# ESP32USBC.net
KiCad netlist of a schematic drawn in Altium Designer
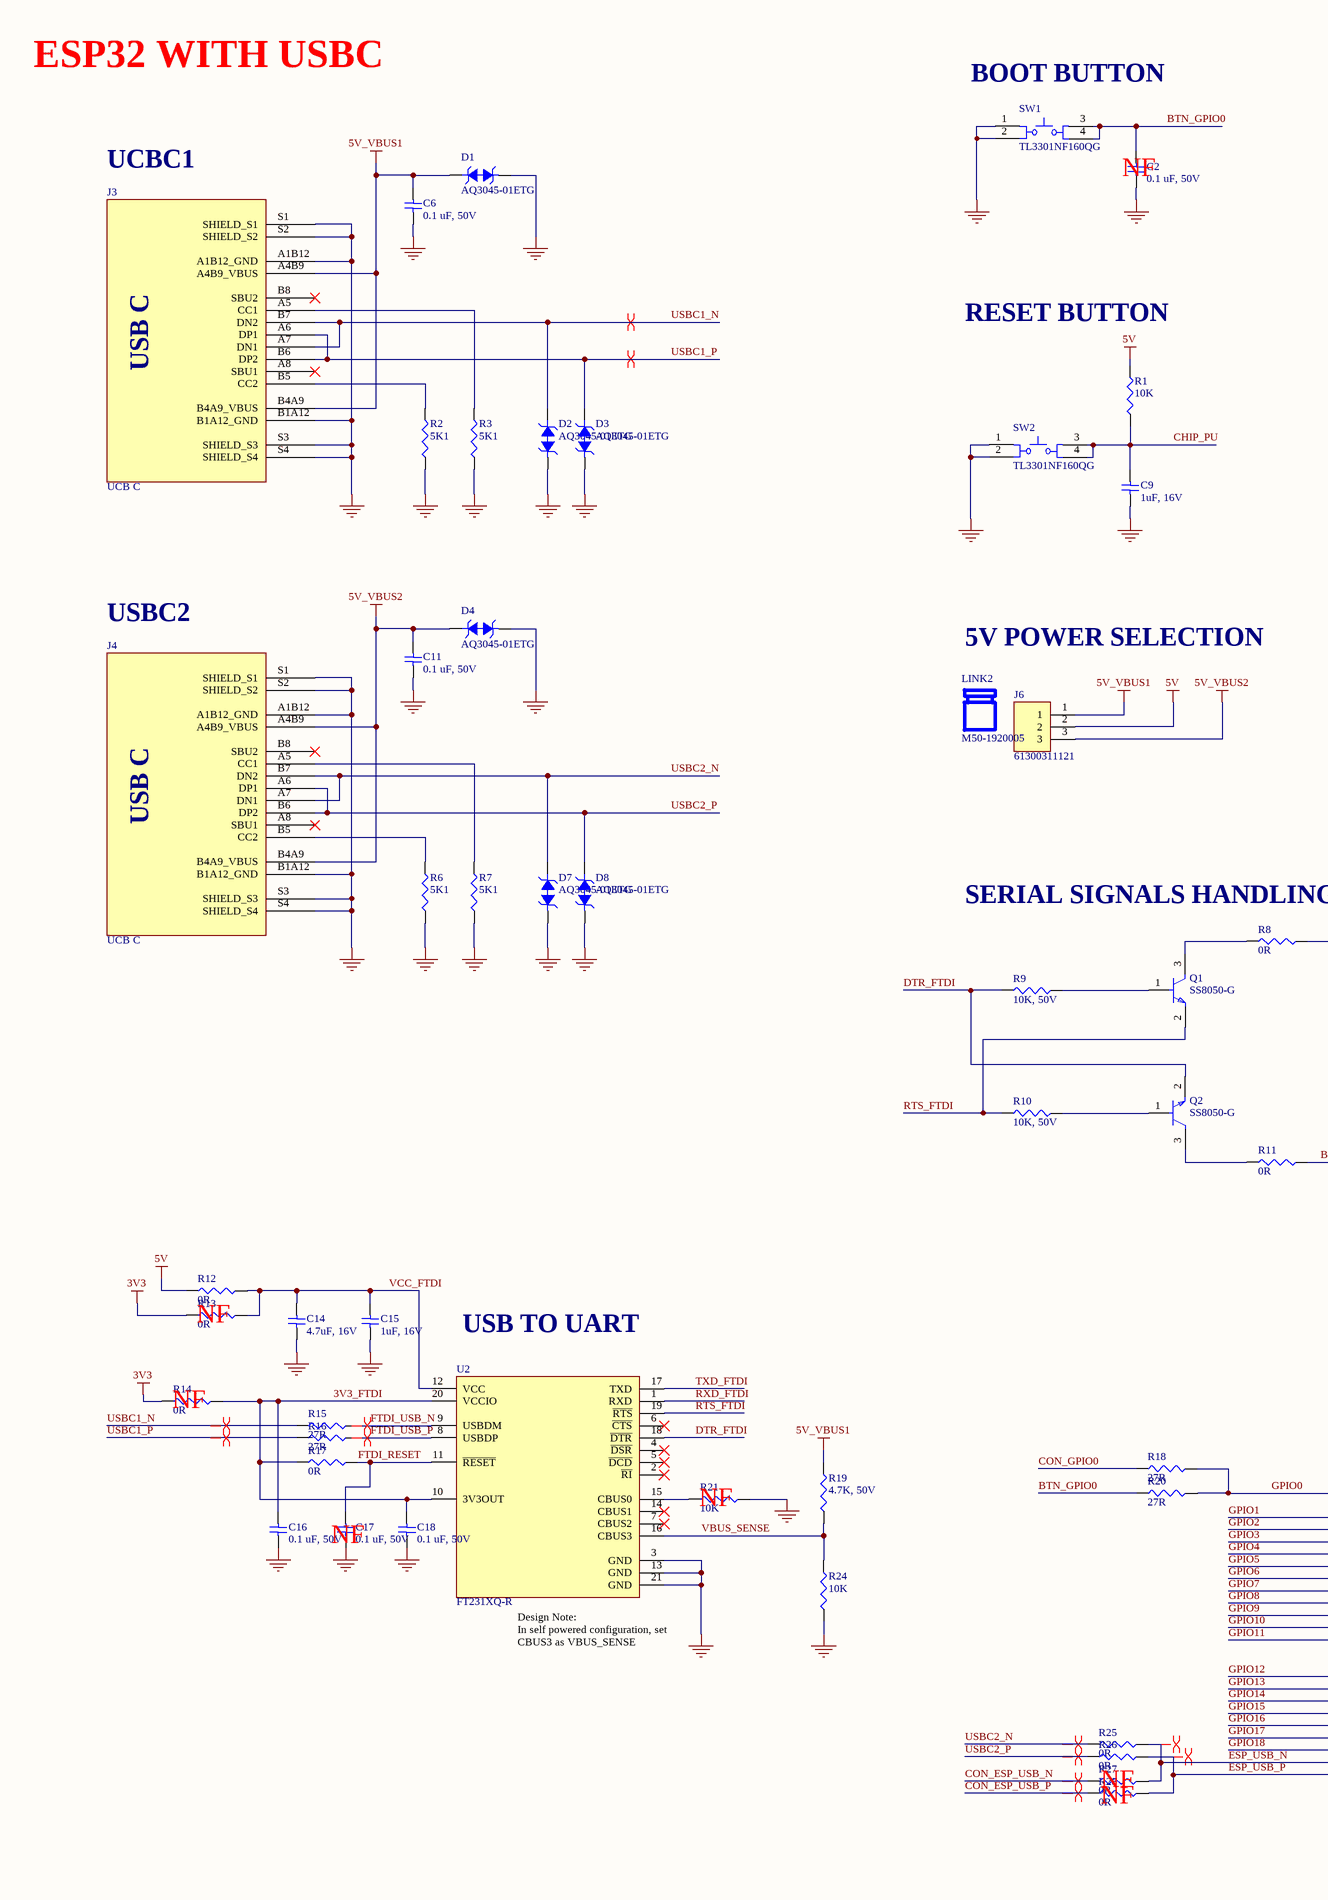
[diagram p0: ESP32USBC.SchDoc, left]
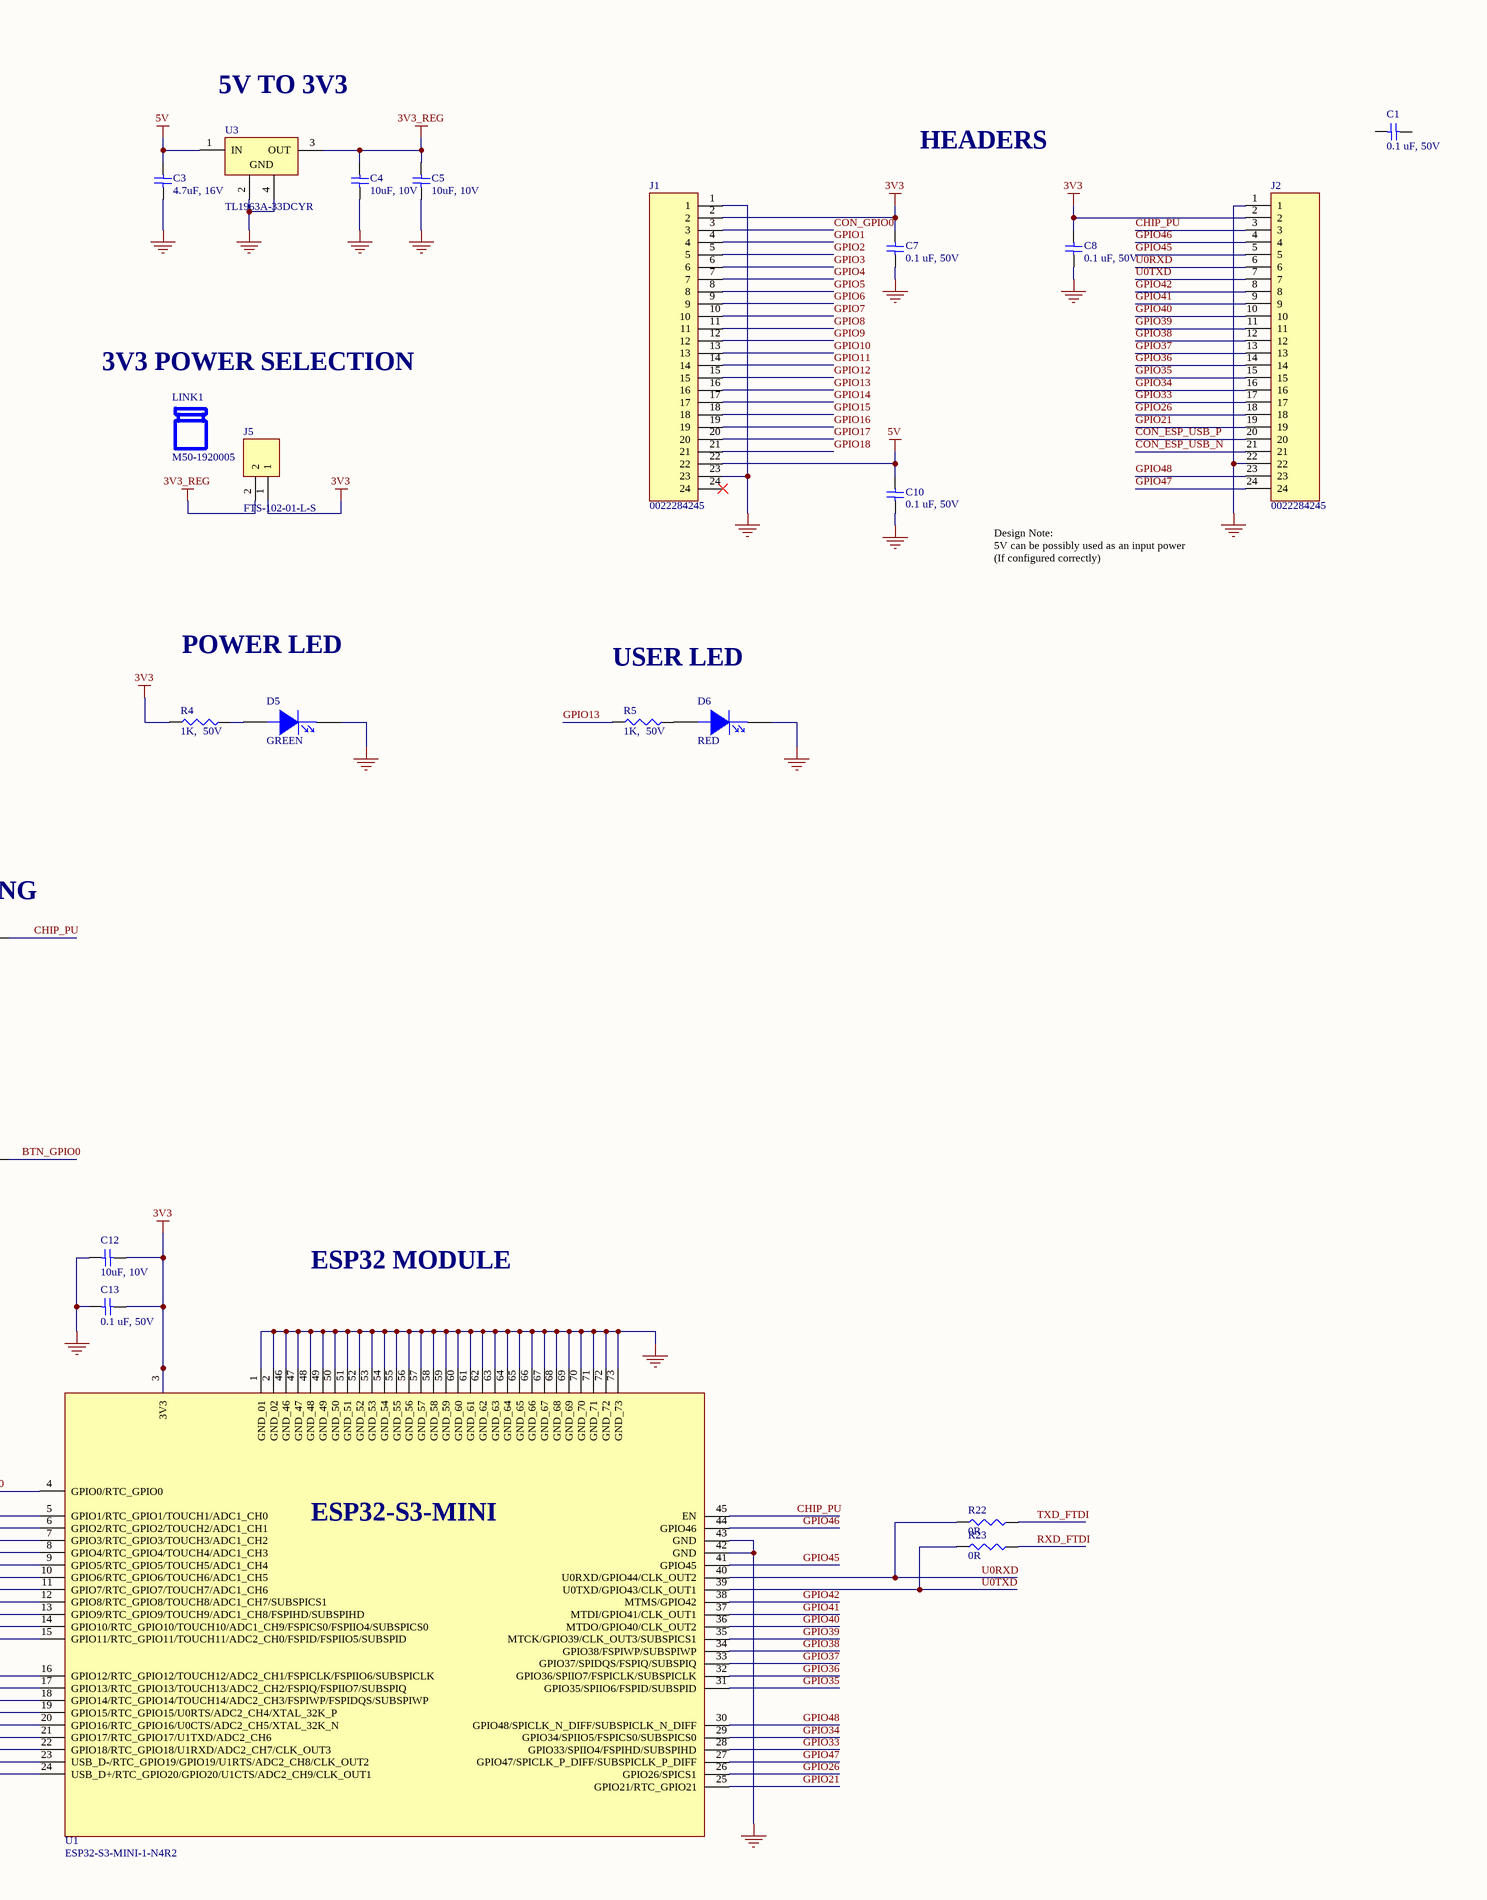
[diagram p1: ESP32USBC.SchDoc, right]

(export (version "E")
  (design (tool "Eeschema 10.0.6"))
  (components
    (comp (ref "C1")
      (value "0.1 uF, 50V")
      (footprint "CAPC1005X55N")
      (fields
        (field (name "MANUFACTURER") "Samsung")
        (field (name "MANUFACTURER PART NUMBER") "CL05B104KB54PNC")
        (field (name "LCSC PART NUMBER") "C307331")
      )
      (libsource (lib "Schlib") (part "CL05B104KB54PNC"))
    )
    (comp (ref "C2")
      (value "0.1 uF, 50V")
      (footprint "CAPC1005X55N")
      (fields
        (field (name "MANUFACTURER") "Samsung")
        (field (name "MANUFACTURER PART NUMBER") "CL05B104KB54PNC")
        (field (name "LCSC PART NUMBER") "C307331")
      )
      (libsource (lib "Schlib") (part "CL05B104KB54PNC"))
    )
    (comp (ref "C3")
      (value "4.7uF, 16V")
      (footprint "CAPC1005X55N")
      (description "CAP CER 4.7UF 16V X5R 0402")
      (fields
        (field (name "MANUFACTURER") "Samsung")
        (field (name "MANUFACTURER PART NUMBER") "CL05A475MO5NUNC")
      )
      (libsource (lib "Schlib") (part "CL05A475MO5NUNC"))
    )
    (comp (ref "C4")
      (value "10uF, 10V")
      (footprint "CAPC1005X55N")
      (description "10V 10uF X5R ±20% 0402 Multilayer Ceramic Capacitors MLCC - SMD/SMT ROHS")
      (fields
        (field (name "MANUFACTURER") "Samsung")
        (field (name "MANUFACTURER PART NUMBER") "CL05A106MP8NUB8")
      )
      (libsource (lib "Schlib") (part "CL05A106MP8NUB8"))
    )
    (comp (ref "C5")
      (value "10uF, 10V")
      (footprint "CAPC1005X55N")
      (description "10V 10uF X5R ±20% 0402 Multilayer Ceramic Capacitors MLCC - SMD/SMT ROHS")
      (fields
        (field (name "MANUFACTURER") "Samsung")
        (field (name "MANUFACTURER PART NUMBER") "CL05A106MP8NUB8")
      )
      (libsource (lib "Schlib") (part "CL05A106MP8NUB8"))
    )
    (comp (ref "C6")
      (value "0.1 uF, 50V")
      (footprint "CAPC1005X55N")
      (fields
        (field (name "MANUFACTURER") "Samsung")
        (field (name "MANUFACTURER PART NUMBER") "CL05B104KB54PNC")
        (field (name "LCSC PART NUMBER") "C307331")
      )
      (libsource (lib "Schlib") (part "CL05B104KB54PNC"))
    )
    (comp (ref "C7")
      (value "0.1 uF, 50V")
      (footprint "CAPC1005X55N")
      (fields
        (field (name "MANUFACTURER") "Samsung")
        (field (name "MANUFACTURER PART NUMBER") "CL05B104KB54PNC")
        (field (name "LCSC PART NUMBER") "C307331")
      )
      (libsource (lib "Schlib") (part "CL05B104KB54PNC"))
    )
    (comp (ref "C8")
      (value "0.1 uF, 50V")
      (footprint "CAPC1005X55N")
      (fields
        (field (name "MANUFACTURER") "Samsung")
        (field (name "MANUFACTURER PART NUMBER") "CL05B104KB54PNC")
        (field (name "LCSC PART NUMBER") "C307331")
      )
      (libsource (lib "Schlib") (part "CL05B104KB54PNC"))
    )
    (comp (ref "C9")
      (value "1uF, 16V")
      (footprint "CAPC1005X55N")
      (description "1 µF ±10% 16V Ceramic Capacitor X5R 0402 (1005 Metric)")
      (fields
        (field (name "MANUFACTURER") "Samsung")
        (field (name "MANUFACTURER PART NUMBER") "CL05A105KO5NNNC")
      )
      (libsource (lib "Schlib") (part "CL05A105KO5NNNC"))
    )
    (comp (ref "C10")
      (value "0.1 uF, 50V")
      (footprint "CAPC1005X55N")
      (fields
        (field (name "MANUFACTURER") "Samsung")
        (field (name "MANUFACTURER PART NUMBER") "CL05B104KB54PNC")
        (field (name "LCSC PART NUMBER") "C307331")
      )
      (libsource (lib "Schlib") (part "CL05B104KB54PNC"))
    )
    (comp (ref "C11")
      (value "0.1 uF, 50V")
      (footprint "CAPC1005X55N")
      (fields
        (field (name "MANUFACTURER") "Samsung")
        (field (name "MANUFACTURER PART NUMBER") "CL05B104KB54PNC")
        (field (name "LCSC PART NUMBER") "C307331")
      )
      (libsource (lib "Schlib") (part "CL05B104KB54PNC"))
    )
    (comp (ref "C12")
      (value "10uF, 10V")
      (footprint "CAPC1005X55N")
      (description "10V 10uF X5R ±20% 0402 Multilayer Ceramic Capacitors MLCC - SMD/SMT ROHS")
      (fields
        (field (name "MANUFACTURER") "Samsung")
        (field (name "MANUFACTURER PART NUMBER") "CL05A106MP8NUB8")
      )
      (libsource (lib "Schlib") (part "CL05A106MP8NUB8"))
    )
    (comp (ref "C13")
      (value "0.1 uF, 50V")
      (footprint "CAPC1005X55N")
      (fields
        (field (name "MANUFACTURER") "Samsung")
        (field (name "MANUFACTURER PART NUMBER") "CL05B104KB54PNC")
        (field (name "LCSC PART NUMBER") "C307331")
      )
      (libsource (lib "Schlib") (part "CL05B104KB54PNC"))
    )
    (comp (ref "C14")
      (value "4.7uF, 16V")
      (footprint "CAPC1005X55N")
      (description "CAP CER 4.7UF 16V X5R 0402")
      (fields
        (field (name "MANUFACTURER") "Samsung")
        (field (name "MANUFACTURER PART NUMBER") "CL05A475MO5NUNC")
      )
      (libsource (lib "Schlib") (part "CL05A475MO5NUNC"))
    )
    (comp (ref "C15")
      (value "1uF, 16V")
      (footprint "CAPC1005X55N")
      (description "1 µF ±10% 16V Ceramic Capacitor X5R 0402 (1005 Metric)")
      (fields
        (field (name "MANUFACTURER") "Samsung")
        (field (name "MANUFACTURER PART NUMBER") "CL05A105KO5NNNC")
      )
      (libsource (lib "Schlib") (part "CL05A105KO5NNNC"))
    )
    (comp (ref "C16")
      (value "0.1 uF, 50V")
      (footprint "CAPC1005X55N")
      (fields
        (field (name "MANUFACTURER") "Samsung")
        (field (name "MANUFACTURER PART NUMBER") "CL05B104KB54PNC")
        (field (name "LCSC PART NUMBER") "C307331")
      )
      (libsource (lib "Schlib") (part "CL05B104KB54PNC"))
    )
    (comp (ref "C17")
      (value "0.1 uF, 50V")
      (footprint "CAPC1005X55N")
      (fields
        (field (name "MANUFACTURER") "Samsung")
        (field (name "MANUFACTURER PART NUMBER") "CL05B104KB54PNC")
        (field (name "LCSC PART NUMBER") "C307331")
      )
      (libsource (lib "Schlib") (part "CL05B104KB54PNC"))
    )
    (comp (ref "C18")
      (value "0.1 uF, 50V")
      (footprint "CAPC1005X55N")
      (fields
        (field (name "MANUFACTURER") "Samsung")
        (field (name "MANUFACTURER PART NUMBER") "CL05B104KB54PNC")
        (field (name "LCSC PART NUMBER") "C307331")
      )
      (libsource (lib "Schlib") (part "CL05B104KB54PNC"))
    )
    (comp (ref "D1")
      (value "AQ3045-01ETG")
      (footprint "SOD882")
      (description "12V Clamp 3A (8/20µs) Ipp Tvs Diode Surface Mount SOD-882")
      (fields (field (name "MANUFACTURER") "Littelfuse") (field (name "LCSC PART NUMBER") "C3710326"))
      (libsource (lib "Schlib") (part "AQ3045-01ETG"))
    )
    (comp (ref "D2")
      (value "AQ3045-01ETG")
      (footprint "SOD882")
      (description "12V Clamp 3A (8/20µs) Ipp Tvs Diode Surface Mount SOD-882")
      (fields (field (name "MANUFACTURER") "Littelfuse") (field (name "LCSC PART NUMBER") "C3710326"))
      (libsource (lib "Schlib") (part "AQ3045-01ETG"))
    )
    (comp (ref "D3")
      (value "AQ3045-01ETG")
      (footprint "SOD882")
      (description "12V Clamp 3A (8/20µs) Ipp Tvs Diode Surface Mount SOD-882")
      (fields (field (name "MANUFACTURER") "Littelfuse") (field (name "LCSC PART NUMBER") "C3710326"))
      (libsource (lib "Schlib") (part "AQ3045-01ETG"))
    )
    (comp (ref "D4")
      (value "AQ3045-01ETG")
      (footprint "SOD882")
      (description "12V Clamp 3A (8/20µs) Ipp Tvs Diode Surface Mount SOD-882")
      (fields (field (name "MANUFACTURER") "Littelfuse") (field (name "LCSC PART NUMBER") "C3710326"))
      (libsource (lib "Schlib") (part "AQ3045-01ETG"))
    )
    (comp (ref "D5")
      (value "GREEN")
      (footprint "LED0402G")
      (description "LED YLW-GRN 0402 SMD")
      (fields
        (field (name "MANUFACTURER") "Vishay")
        (field (name "MANUFACTURER PART NUMBER") "VLMG1500-GS08")
      )
      (libsource (lib "Schlib") (part "VLMG1500-GS08"))
    )
    (comp (ref "D6")
      (value "RED")
      (footprint "LED0402R")
      (description "LED RED 0402 SMD")
      (fields
        (field (name "MANUFACTURER") "Vishay")
        (field (name "MANUFACTURER PART NUMBER") "VLMS1500-GS08")
      )
      (libsource (lib "Schlib") (part "VLMS1500-GS08"))
    )
    (comp (ref "D7")
      (value "AQ3045-01ETG")
      (footprint "SOD882")
      (description "12V Clamp 3A (8/20µs) Ipp Tvs Diode Surface Mount SOD-882")
      (fields (field (name "MANUFACTURER") "Littelfuse") (field (name "LCSC PART NUMBER") "C3710326"))
      (libsource (lib "Schlib") (part "AQ3045-01ETG"))
    )
    (comp (ref "D8")
      (value "AQ3045-01ETG")
      (footprint "SOD882")
      (description "12V Clamp 3A (8/20µs) Ipp Tvs Diode Surface Mount SOD-882")
      (fields (field (name "MANUFACTURER") "Littelfuse") (field (name "LCSC PART NUMBER") "C3710326"))
      (libsource (lib "Schlib") (part "AQ3045-01ETG"))
    )
    (comp (ref "J1")
      (value "0022284245")
      (footprint "HDR_1x24_2.54MM")
      (description "CONN HEADER VERT 24POS 2.54MM")
      (fields (field (name "MANUFACTURER") "Molex") (field (name "LCSC PART NUMBER") "C7145888"))
      (libsource (lib "Schlib") (part "0022284245"))
    )
    (comp (ref "J2")
      (value "0022284245")
      (footprint "HDR_1x24_2.54MM")
      (description "CONN HEADER VERT 24POS 2.54MM")
      (fields (field (name "MANUFACTURER") "Molex") (field (name "LCSC PART NUMBER") "C7145888"))
      (libsource (lib "") (part "0022284245_1"))
    )
    (comp (ref "J3")
      (value "UCB C")
      (footprint "FP-2171790001-MFG")
      (fields
        (field (name "MANUFACTURER") "Molex")
        (field (name "MANUFACTURER PART NUMBER") "217179-0001")
        (field (name "LCSC PART NUMBER") "C3197684")
      )
      (libsource (lib "Schlib") (part "217179-0001"))
    )
    (comp (ref "J4")
      (value "UCB C")
      (footprint "FP-2171790001-MFG")
      (fields
        (field (name "MANUFACTURER") "Molex")
        (field (name "MANUFACTURER PART NUMBER") "217179-0001")
        (field (name "LCSC PART NUMBER") "C3197684")
      )
      (libsource (lib "Schlib") (part "217179-0001"))
    )
    (comp (ref "J5")
      (value "FTS-102-01-L-S")
      (footprint "HDR_1x2_1.27MM")
      (description "Board Connector, 2 Contact(s), 1 Row(s), Male, Straight, Solder Terminal")
      (fields (field (name "MANUFACTURER") "Samtec") (field (name "LCSC PART NUMBER") "C7194937"))
      (libsource (lib "Schlib") (part "FTS-102-01-L-S"))
    )
    (comp (ref "J6")
      (value "61300311121")
      (footprint "HDR_1x3_2.54MM")
      (description "CONN HEADER VERT 3POS 2.54MM")
      (fields (field (name "MANUFACTURER") "Wurth Electronics"))
      (libsource (lib "Schlib") (part "61300311121"))
    )
    (comp (ref "LINK1")
      (value "M50-1920005")
      (description "CONN SHUNT 1.27MM RED")
      (fields (field (name "MANUFACTURER") "Harwin") (field (name "LCSC PART NUMBER") "C6985646"))
      (libsource (lib "Schlib") (part "M50-1920005"))
    )
    (comp (ref "LINK2")
      (value "M50-1920005")
      (description "CONN SHUNT 1.27MM RED")
      (fields (field (name "MANUFACTURER") "Harwin") (field (name "LCSC PART NUMBER") "C6985646"))
      (libsource (lib "Schlib") (part "M50-1920005"))
    )
    (comp (ref "Q1")
      (value "SS8050-G")
      (footprint "FP-SS8050-G-IPC_B")
      (description "TRANS NPN 25V 1.5A SOT23-3")
      (fields (field (name "MANUFACTURER") "Comchip") (field (name "LCSC PART NUMBER") "C164886"))
      (libsource (lib "Schlib") (part "SS8050-G"))
    )
    (comp (ref "Q2")
      (value "SS8050-G")
      (footprint "FP-SS8050-G-IPC_B")
      (description "TRANS NPN 25V 1.5A SOT23-3")
      (fields (field (name "MANUFACTURER") "Comchip") (field (name "LCSC PART NUMBER") "C164886"))
      (libsource (lib "Schlib") (part "SS8050-G"))
    )
    (comp (ref "R1")
      (value "10K")
      (footprint "RESC1005X40N")
      (fields
        (field (name "MANUFACTURER") "Samsung")
        (field (name "MANUFACTURER PART NUMBER") "RC1005F103CS")
        (field (name "TOLERANCE") "1%")
      )
      (libsource (lib "Schlib") (part "RC1005F103CS"))
    )
    (comp (ref "R2")
      (value "5K1")
      (footprint "RESC1005X40N")
      (description "5.1 kOhms ±1% 0.063W, 1/16W Chip Resistor 0402 (1005 Metric) Moisture Resistant Thick Film")
      (fields
        (field (name "MANUFACTURER") "Yageo")
        (field (name "MANUFACTURER PART NUMBER") "RC0402FR-075K1L")
      )
      (libsource (lib "Schlib") (part "RC0402FR-075K1L"))
    )
    (comp (ref "R3")
      (value "5K1")
      (footprint "RESC1005X40N")
      (description "5.1 kOhms ±1% 0.063W, 1/16W Chip Resistor 0402 (1005 Metric) Moisture Resistant Thick Film")
      (fields
        (field (name "MANUFACTURER") "Yageo")
        (field (name "MANUFACTURER PART NUMBER") "RC0402FR-075K1L")
      )
      (libsource (lib "Schlib") (part "RC0402FR-075K1L"))
    )
    (comp (ref "R4")
      (value "1K,  50V")
      (footprint "RESC1005X40N")
      (description "RES 1K OHM 5% 1/16W 0402")
      (fields
        (field (name "MANUFACTURER") "Yageo")
        (field (name "MANUFACTURER PART NUMBER") "RC0402JR-071KL")
      )
      (libsource (lib "Schlib") (part "RC0402JR-071KL"))
    )
    (comp (ref "R5")
      (value "1K,  50V")
      (footprint "RESC1005X40N")
      (description "RES 1K OHM 5% 1/16W 0402")
      (fields
        (field (name "MANUFACTURER") "Yageo")
        (field (name "MANUFACTURER PART NUMBER") "RC0402JR-071KL")
      )
      (libsource (lib "Schlib") (part "RC0402JR-071KL"))
    )
    (comp (ref "R6")
      (value "5K1")
      (footprint "RESC1005X40N")
      (description "5.1 kOhms ±1% 0.063W, 1/16W Chip Resistor 0402 (1005 Metric) Moisture Resistant Thick Film")
      (fields
        (field (name "MANUFACTURER") "Yageo")
        (field (name "MANUFACTURER PART NUMBER") "RC0402FR-075K1L")
      )
      (libsource (lib "Schlib") (part "RC0402FR-075K1L"))
    )
    (comp (ref "R7")
      (value "5K1")
      (footprint "RESC1005X40N")
      (description "5.1 kOhms ±1% 0.063W, 1/16W Chip Resistor 0402 (1005 Metric) Moisture Resistant Thick Film")
      (fields
        (field (name "MANUFACTURER") "Yageo")
        (field (name "MANUFACTURER PART NUMBER") "RC0402FR-075K1L")
      )
      (libsource (lib "Schlib") (part "RC0402FR-075K1L"))
    )
    (comp (ref "R8")
      (value "0R")
      (footprint "RESC1005X40N")
      (description "RES 0 OHM JUMPER 1/16W 0402")
      (fields
        (field (name "MANUFACTURER") "Yageo")
        (field (name "MANUFACTURER PART NUMBER") "RC0402JR-070RL")
      )
      (libsource (lib "Schlib") (part "RC0402JR-070RL"))
    )
    (comp (ref "R9")
      (value "10K, 50V")
      (footprint "RESC1005X40N")
      (description "RES 10K OHM 1% 1/16W 0402")
      (fields
        (field (name "MANUFACTURER") "Yageo")
        (field (name "MANUFACTURER PART NUMBER") "RC0402FR-0710KL")
      )
      (libsource (lib "Schlib") (part "RC0402FR-0710KL"))
    )
    (comp (ref "R10")
      (value "10K, 50V")
      (footprint "RESC1005X40N")
      (description "RES 10K OHM 1% 1/16W 0402")
      (fields
        (field (name "MANUFACTURER") "Yageo")
        (field (name "MANUFACTURER PART NUMBER") "RC0402FR-0710KL")
      )
      (libsource (lib "Schlib") (part "RC0402FR-0710KL"))
    )
    (comp (ref "R11")
      (value "0R")
      (footprint "RESC1005X40N")
      (description "RES 0 OHM JUMPER 1/16W 0402")
      (fields
        (field (name "MANUFACTURER") "Yageo")
        (field (name "MANUFACTURER PART NUMBER") "RC0402JR-070RL")
      )
      (libsource (lib "Schlib") (part "RC0402JR-070RL"))
    )
    (comp (ref "R12")
      (value "0R")
      (footprint "RESC1005X40N")
      (description "RES 0 OHM JUMPER 1/16W 0402")
      (fields
        (field (name "MANUFACTURER") "Yageo")
        (field (name "MANUFACTURER PART NUMBER") "RC0402JR-070RL")
      )
      (libsource (lib "Schlib") (part "RC0402JR-070RL"))
    )
    (comp (ref "R13")
      (value "0R")
      (footprint "RESC1005X40N")
      (description "RES 0 OHM JUMPER 1/16W 0402")
      (fields
        (field (name "MANUFACTURER") "Yageo")
        (field (name "MANUFACTURER PART NUMBER") "RC0402JR-070RL")
      )
      (libsource (lib "Schlib") (part "RC0402JR-070RL"))
    )
    (comp (ref "R14")
      (value "0R")
      (footprint "RESC1005X40N")
      (description "RES 0 OHM JUMPER 1/16W 0402")
      (fields
        (field (name "MANUFACTURER") "Yageo")
        (field (name "MANUFACTURER PART NUMBER") "RC0402JR-070RL")
      )
      (libsource (lib "Schlib") (part "RC0402JR-070RL"))
    )
    (comp (ref "R15")
      (value "27R")
      (footprint "RESC1005X40N")
      (description "27.4 Ohms ±1% 0.1W, 1/10W Chip Resistor 0402 (1005 Metric) Automotive AEC-Q200 Thick Film")
      (fields
        (field (name "MANUFACTURER") "Panasonic")
        (field (name "MANUFACTURER PART NUMBER") "ERJ-2RKF27R4X")
      )
      (libsource (lib "Schlib") (part "ERJ-2RKF27R4X"))
    )
    (comp (ref "R16")
      (value "27R")
      (footprint "RESC1005X40N")
      (description "27.4 Ohms ±1% 0.1W, 1/10W Chip Resistor 0402 (1005 Metric) Automotive AEC-Q200 Thick Film")
      (fields
        (field (name "MANUFACTURER") "Panasonic")
        (field (name "MANUFACTURER PART NUMBER") "ERJ-2RKF27R4X")
      )
      (libsource (lib "Schlib") (part "ERJ-2RKF27R4X"))
    )
    (comp (ref "R17")
      (value "0R")
      (footprint "RESC1005X40N")
      (description "RES 0 OHM JUMPER 1/16W 0402")
      (fields
        (field (name "MANUFACTURER") "Yageo")
        (field (name "MANUFACTURER PART NUMBER") "RC0402JR-070RL")
      )
      (libsource (lib "Schlib") (part "RC0402JR-070RL"))
    )
    (comp (ref "R18")
      (value "27R")
      (footprint "RESC1005X40N")
      (description "27.4 Ohms ±1% 0.1W, 1/10W Chip Resistor 0402 (1005 Metric) Automotive AEC-Q200 Thick Film")
      (fields
        (field (name "MANUFACTURER") "Panasonic")
        (field (name "MANUFACTURER PART NUMBER") "ERJ-2RKF27R4X")
      )
      (libsource (lib "Schlib") (part "ERJ-2RKF27R4X"))
    )
    (comp (ref "R19")
      (value "4.7K, 50V")
      (footprint "RESC1005X40N")
      (description "RES 4.7K OHM 5% 1/16W 0402")
      (fields
        (field (name "MANUFACTURER") "Yageo")
        (field (name "MANUFACTURER PART NUMBER") "RC0402JR-074K7L")
      )
      (libsource (lib "Schlib") (part "RC0402JR-074K7L"))
    )
    (comp (ref "R20")
      (value "27R")
      (footprint "RESC1005X40N")
      (description "27.4 Ohms ±1% 0.1W, 1/10W Chip Resistor 0402 (1005 Metric) Automotive AEC-Q200 Thick Film")
      (fields
        (field (name "MANUFACTURER") "Panasonic")
        (field (name "MANUFACTURER PART NUMBER") "ERJ-2RKF27R4X")
      )
      (libsource (lib "Schlib") (part "ERJ-2RKF27R4X"))
    )
    (comp (ref "R21")
      (value "10K")
      (footprint "RESC1005X40N")
      (fields
        (field (name "MANUFACTURER") "Samsung")
        (field (name "MANUFACTURER PART NUMBER") "RC1005F103CS")
        (field (name "TOLERANCE") "1%")
      )
      (libsource (lib "Schlib") (part "RC1005F103CS"))
    )
    (comp (ref "R22")
      (value "0R")
      (footprint "RESC1005X40N")
      (description "RES 0 OHM JUMPER 1/16W 0402")
      (fields
        (field (name "MANUFACTURER") "Yageo")
        (field (name "MANUFACTURER PART NUMBER") "RC0402JR-070RL")
      )
      (libsource (lib "Schlib") (part "RC0402JR-070RL"))
    )
    (comp (ref "R23")
      (value "0R")
      (footprint "RESC1005X40N")
      (description "RES 0 OHM JUMPER 1/16W 0402")
      (fields
        (field (name "MANUFACTURER") "Yageo")
        (field (name "MANUFACTURER PART NUMBER") "RC0402JR-070RL")
      )
      (libsource (lib "Schlib") (part "RC0402JR-070RL"))
    )
    (comp (ref "R24")
      (value "10K")
      (footprint "RESC1005X40N")
      (fields
        (field (name "MANUFACTURER") "Samsung")
        (field (name "MANUFACTURER PART NUMBER") "RC1005F103CS")
        (field (name "TOLERANCE") "1%")
      )
      (libsource (lib "Schlib") (part "RC1005F103CS"))
    )
    (comp (ref "R25")
      (value "0R")
      (footprint "RESC1005X40N")
      (description "RES 0 OHM JUMPER 1/16W 0402")
      (fields
        (field (name "MANUFACTURER") "Yageo")
        (field (name "MANUFACTURER PART NUMBER") "RC0402JR-070RL")
      )
      (libsource (lib "Schlib") (part "RC0402JR-070RL"))
    )
    (comp (ref "R26")
      (value "0R")
      (footprint "RESC1005X40N")
      (description "RES 0 OHM JUMPER 1/16W 0402")
      (fields
        (field (name "MANUFACTURER") "Yageo")
        (field (name "MANUFACTURER PART NUMBER") "RC0402JR-070RL")
      )
      (libsource (lib "Schlib") (part "RC0402JR-070RL"))
    )
    (comp (ref "R27")
      (value "0R")
      (footprint "RESC1005X40N")
      (description "RES 0 OHM JUMPER 1/16W 0402")
      (fields
        (field (name "MANUFACTURER") "Yageo")
        (field (name "MANUFACTURER PART NUMBER") "RC0402JR-070RL")
      )
      (libsource (lib "Schlib") (part "RC0402JR-070RL"))
    )
    (comp (ref "R28")
      (value "0R")
      (footprint "RESC1005X40N")
      (description "RES 0 OHM JUMPER 1/16W 0402")
      (fields
        (field (name "MANUFACTURER") "Yageo")
        (field (name "MANUFACTURER PART NUMBER") "RC0402JR-070RL")
      )
      (libsource (lib "Schlib") (part "RC0402JR-070RL"))
    )
    (comp (ref "SW1")
      (value "TL3301NF160QG")
      (footprint "ESWI-TL3301NF160QG_V")
      (description "Round Button 50mA Standing paste SPST - normally open 160gf 12V Tactile Switches ROHS")
      (fields (field (name "MANUFACTURER") "E-Switch") (field (name "LCSC PART NUMBER") "C7124061"))
      (libsource (lib "Schlib") (part "TL3301NF160QG"))
    )
    (comp (ref "SW2")
      (value "TL3301NF160QG")
      (footprint "ESWI-TL3301NF160QG_V")
      (description "Round Button 50mA Standing paste SPST - normally open 160gf 12V Tactile Switches ROHS")
      (fields (field (name "MANUFACTURER") "E-Switch") (field (name "LCSC PART NUMBER") "C7124061"))
      (libsource (lib "Schlib") (part "TL3301NF160QG"))
    )
    (comp (ref "U1")
      (value "ESP32-S3-MINI-1-N4R2")
      (footprint "XCVR_ESP32-S3-MINI-1-N4R2")
      (description "Telecom Circuit, 1-Func")
      (fields (field (name "MANUFACTURER") "Espressif Systems") (field (name "LCSC PART NUMBER") "C3013941"))
      (libsource (lib "Schlib") (part "ESP32-S3-MINI-1-N4R2"))
    )
    (comp (ref "U2")
      (value "FT231XQ-R")
      (footprint "FP-QFN-20-IPC_B")
      (description "IC USB SERIAL FULL UART 20QFN")
      (fields (field (name "MANUFACTURER") "FTDI") (field (name "LCSC PART NUMBER") "C132159"))
      (libsource (lib "Schlib") (part "FT231XQ-R"))
    )
    (comp (ref "U3")
      (value "TL1963A-33DCYR")
      (footprint "DCY0004A_M")
      (description "IC REG LINEAR 3.3V 1.5A SOT223-4")
      (fields (field (name "MANUFACTURER") "Texas Instruments") (field (name "LCSC PART NUMBER") "C181262"))
      (libsource (lib "Schlib") (part "TL1963A-33DCYR"))
    )
  )
  (nets
    (net (code "1") (name "/3V3_FTDI") (class "Default")
      (node (ref "C16") (pin "1") (pinfunction "1_1") (pintype "passive"))
      (node (ref "C18") (pin "1") (pinfunction "1_1") (pintype "passive"))
      (node (ref "R14") (pin "2") (pinfunction "2_2") (pintype "passive"))
      (node (ref "R17") (pin "1") (pinfunction "1_1") (pintype "passive"))
      (node (ref "U2") (pin "10") (pinfunction "3V3OUT_10") (pintype "passive"))
      (node (ref "U2") (pin "20") (pinfunction "VCCIO_20") (pintype "passive"))
    )
    (net (code "2") (name "/BTN_GPIO0") (class "Default")
      (node (ref "C2") (pin "2") (pinfunction "2_2") (pintype "passive"))
      (node (ref "R11") (pin "2") (pinfunction "2_2") (pintype "passive"))
      (node (ref "R20") (pin "1") (pinfunction "1_1") (pintype "passive"))
      (node (ref "SW1") (pin "3") (pinfunction "3_3") (pintype "passive"))
      (node (ref "SW1") (pin "4") (pinfunction "4_4") (pintype "passive"))
    )
    (net (code "3") (name "/CHIP_PU") (class "Default")
      (node (ref "C9") (pin "2") (pinfunction "2_2") (pintype "passive"))
      (node (ref "J2") (pin "3") (pinfunction "3_3") (pintype "passive"))
      (node (ref "R1") (pin "1") (pinfunction "1_1") (pintype "passive"))
      (node (ref "R8") (pin "2") (pinfunction "2_2") (pintype "passive"))
      (node (ref "SW2") (pin "3") (pinfunction "3_3") (pintype "passive"))
      (node (ref "SW2") (pin "4") (pinfunction "4_4") (pintype "passive"))
      (node (ref "U1") (pin "45") (pinfunction "EN_45") (pintype "passive"))
    )
    (net (code "4") (name "/CON_ESP_USB_N") (class "Default")
      (node (ref "J2") (pin "21") (pinfunction "21_21") (pintype "passive"))
      (node (ref "R27") (pin "1") (pinfunction "1_1") (pintype "passive"))
    )
    (net (code "5") (name "/CON_ESP_USB_P") (class "Default")
      (node (ref "J2") (pin "20") (pinfunction "20_20") (pintype "passive"))
      (node (ref "R28") (pin "1") (pinfunction "1_1") (pintype "passive"))
    )
    (net (code "6") (name "/CON_GPIO0") (class "Default")
      (node (ref "J1") (pin "3") (pinfunction "3_3") (pintype "passive"))
      (node (ref "R18") (pin "1") (pinfunction "1_1") (pintype "passive"))
    )
    (net (code "7") (name "/DTR_FTDI") (class "Default")
      (node (ref "Q2") (pin "2") (pinfunction "E_2") (pintype "passive"))
      (node (ref "R9") (pin "1") (pinfunction "1_1") (pintype "passive"))
      (node (ref "U2") (pin "18") (pinfunction "~{DTR}_18") (pintype "passive"))
    )
    (net (code "8") (name "/ESP_USB_N") (class "Default")
      (node (ref "R25") (pin "2") (pinfunction "2_2") (pintype "passive"))
      (node (ref "R27") (pin "2") (pinfunction "2_2") (pintype "passive"))
      (node (ref "U1") (pin "23") (pinfunction "USB_D-/RTC_GPIO19/GPIO19/U1RTS/ADC2_CH8/CLK_OUT2_23") (pintype "passive"))
    )
    (net (code "9") (name "/ESP_USB_P") (class "Default")
      (node (ref "R26") (pin "2") (pinfunction "2_2") (pintype "passive"))
      (node (ref "R28") (pin "2") (pinfunction "2_2") (pintype "passive"))
      (node (ref "U1") (pin "24") (pinfunction "USB_D+/RTC_GPIO20/GPIO20/U1CTS/ADC2_CH9/CLK_OUT1_24") (pintype "passive"))
    )
    (net (code "10") (name "/FTDI_RESET") (class "Default")
      (node (ref "C17") (pin "1") (pinfunction "1_1") (pintype "passive"))
      (node (ref "R17") (pin "2") (pinfunction "2_2") (pintype "passive"))
      (node (ref "U2") (pin "11") (pinfunction "~{RESET}_11") (pintype "passive"))
    )
    (net (code "11") (name "/FTDI_USB_N") (class "Default")
      (node (ref "R15") (pin "2") (pinfunction "2_2") (pintype "passive"))
      (node (ref "U2") (pin "9") (pinfunction "USBDM_9") (pintype "passive"))
    )
    (net (code "12") (name "/FTDI_USB_P") (class "Default")
      (node (ref "R16") (pin "2") (pinfunction "2_2") (pintype "passive"))
      (node (ref "U2") (pin "8") (pinfunction "USBDP_8") (pintype "passive"))
    )
    (net (code "13") (name "/GPIO0") (class "Default")
      (node (ref "R18") (pin "2") (pinfunction "2_2") (pintype "passive"))
      (node (ref "R20") (pin "2") (pinfunction "2_2") (pintype "passive"))
      (node (ref "U1") (pin "4") (pinfunction "GPIO0/RTC_GPIO0_4") (pintype "passive"))
    )
    (net (code "14") (name "/GPIO1") (class "Default")
      (node (ref "J1") (pin "4") (pinfunction "4_4") (pintype "passive"))
      (node (ref "U1") (pin "5") (pinfunction "GPIO1/RTC_GPIO1/TOUCH1/ADC1_CH0_5") (pintype "passive"))
    )
    (net (code "15") (name "/GPIO2") (class "Default")
      (node (ref "J1") (pin "5") (pinfunction "5_5") (pintype "passive"))
      (node (ref "U1") (pin "6") (pinfunction "GPIO2/RTC_GPIO2/TOUCH2/ADC1_CH1_6") (pintype "passive"))
    )
    (net (code "16") (name "/GPIO3") (class "Default")
      (node (ref "J1") (pin "6") (pinfunction "6_6") (pintype "passive"))
      (node (ref "U1") (pin "7") (pinfunction "GPIO3/RTC_GPIO3/TOUCH3/ADC1_CH2_7") (pintype "passive"))
    )
    (net (code "17") (name "/GPIO4") (class "Default")
      (node (ref "J1") (pin "7") (pinfunction "7_7") (pintype "passive"))
      (node (ref "U1") (pin "8") (pinfunction "GPIO4/RTC_GPIO4/TOUCH4/ADC1_CH3_8") (pintype "passive"))
    )
    (net (code "18") (name "/GPIO5") (class "Default")
      (node (ref "J1") (pin "8") (pinfunction "8_8") (pintype "passive"))
      (node (ref "U1") (pin "9") (pinfunction "GPIO5/RTC_GPIO5/TOUCH5/ADC1_CH4_9") (pintype "passive"))
    )
    (net (code "19") (name "/GPIO6") (class "Default")
      (node (ref "J1") (pin "9") (pinfunction "9_9") (pintype "passive"))
      (node (ref "U1") (pin "10") (pinfunction "GPIO6/RTC_GPIO6/TOUCH6/ADC1_CH5_10") (pintype "passive"))
    )
    (net (code "20") (name "/GPIO7") (class "Default")
      (node (ref "J1") (pin "10") (pinfunction "10_10") (pintype "passive"))
      (node (ref "U1") (pin "11") (pinfunction "GPIO7/RTC_GPIO7/TOUCH7/ADC1_CH6_11") (pintype "passive"))
    )
    (net (code "21") (name "/GPIO8") (class "Default")
      (node (ref "J1") (pin "11") (pinfunction "11_11") (pintype "passive"))
      (node (ref "U1") (pin "12") (pinfunction "GPIO8/RTC_GPIO8/TOUCH8/ADC1_CH7/SUBSPICS1_12") (pintype "passive"))
    )
    (net (code "22") (name "/GPIO9") (class "Default")
      (node (ref "J1") (pin "12") (pinfunction "12_12") (pintype "passive"))
      (node (ref "U1") (pin "13") (pinfunction "GPIO9/RTC_GPIO9/TOUCH9/ADC1_CH8/FSPIHD/SUBSPIHD_13") (pintype "passive"))
    )
    (net (code "23") (name "/GPIO10") (class "Default")
      (node (ref "J1") (pin "13") (pinfunction "13_13") (pintype "passive"))
      (node (ref "U1") (pin "14") (pinfunction "GPIO10/RTC_GPIO10/TOUCH10/ADC1_CH9/FSPICS0/FSPIIO4/SUBSPICS0_14") (pintype "passive"))
    )
    (net (code "24") (name "/GPIO11") (class "Default")
      (node (ref "J1") (pin "14") (pinfunction "14_14") (pintype "passive"))
      (node (ref "U1") (pin "15") (pinfunction "GPIO11/RTC_GPIO11/TOUCH11/ADC2_CH0/FSPID/FSPIIO5/SUBSPID_15") (pintype "passive"))
    )
    (net (code "25") (name "/GPIO12") (class "Default")
      (node (ref "J1") (pin "15") (pinfunction "15_15") (pintype "passive"))
      (node (ref "U1") (pin "16") (pinfunction "GPIO12/RTC_GPIO12/TOUCH12/ADC2_CH1/FSPICLK/FSPIIO6/SUBSPICLK_16") (pintype "passive"))
    )
    (net (code "26") (name "/GPIO13") (class "Default")
      (node (ref "J1") (pin "16") (pinfunction "16_16") (pintype "passive"))
      (node (ref "R5") (pin "2") (pinfunction "2_2") (pintype "passive"))
      (node (ref "U1") (pin "17") (pinfunction "GPIO13/RTC_GPIO13/TOUCH13/ADC2_CH2/FSPIQ/FSPIIO7/SUBSPIQ_17") (pintype "passive"))
    )
    (net (code "27") (name "/GPIO14") (class "Default")
      (node (ref "J1") (pin "17") (pinfunction "17_17") (pintype "passive"))
      (node (ref "U1") (pin "18") (pinfunction "GPIO14/RTC_GPIO14/TOUCH14/ADC2_CH3/FSPIWP/FSPIDQS/SUBSPIWP_18") (pintype "passive"))
    )
    (net (code "28") (name "/GPIO15") (class "Default")
      (node (ref "J1") (pin "18") (pinfunction "18_18") (pintype "passive"))
      (node (ref "U1") (pin "19") (pinfunction "GPIO15/RTC_GPIO15/U0RTS/ADC2_CH4/XTAL_32K_P_19") (pintype "passive"))
    )
    (net (code "29") (name "/GPIO16") (class "Default")
      (node (ref "J1") (pin "19") (pinfunction "19_19") (pintype "passive"))
      (node (ref "U1") (pin "20") (pinfunction "GPIO16/RTC_GPIO16/U0CTS/ADC2_CH5/XTAL_32K_N_20") (pintype "passive"))
    )
    (net (code "30") (name "/GPIO17") (class "Default")
      (node (ref "J1") (pin "20") (pinfunction "20_20") (pintype "passive"))
      (node (ref "U1") (pin "21") (pinfunction "GPIO17/RTC_GPIO17/U1TXD/ADC2_CH6_21") (pintype "passive"))
    )
    (net (code "31") (name "/GPIO18") (class "Default")
      (node (ref "J1") (pin "21") (pinfunction "21_21") (pintype "passive"))
      (node (ref "U1") (pin "22") (pinfunction "GPIO18/RTC_GPIO18/U1RXD/ADC2_CH7/CLK_OUT3_22") (pintype "passive"))
    )
    (net (code "32") (name "/GPIO21") (class "Default")
      (node (ref "J2") (pin "19") (pinfunction "19_19") (pintype "passive"))
      (node (ref "U1") (pin "25") (pinfunction "GPIO21/RTC_GPIO21_25") (pintype "passive"))
    )
    (net (code "33") (name "/GPIO26") (class "Default")
      (node (ref "J2") (pin "18") (pinfunction "18_18") (pintype "passive"))
      (node (ref "U1") (pin "26") (pinfunction "GPIO26/SPICS1_26") (pintype "passive"))
    )
    (net (code "34") (name "/GPIO33") (class "Default")
      (node (ref "J2") (pin "17") (pinfunction "17_17") (pintype "passive"))
      (node (ref "U1") (pin "28") (pinfunction "GPIO33/SPIIO4/FSPIHD/SUBSPIHD_28") (pintype "passive"))
    )
    (net (code "35") (name "/GPIO34") (class "Default")
      (node (ref "J2") (pin "16") (pinfunction "16_16") (pintype "passive"))
      (node (ref "U1") (pin "29") (pinfunction "GPIO34/SPIIO5/FSPICS0/SUBSPICS0_29") (pintype "passive"))
    )
    (net (code "36") (name "/GPIO35") (class "Default")
      (node (ref "J2") (pin "15") (pinfunction "15_15") (pintype "passive"))
      (node (ref "U1") (pin "31") (pinfunction "GPIO35/SPIIO6/FSPID/SUBSPID_31") (pintype "passive"))
    )
    (net (code "37") (name "/GPIO36") (class "Default")
      (node (ref "J2") (pin "14") (pinfunction "14_14") (pintype "passive"))
      (node (ref "U1") (pin "32") (pinfunction "GPIO36/SPIIO7/FSPICLK/SUBSPICLK_32") (pintype "passive"))
    )
    (net (code "38") (name "/GPIO37") (class "Default")
      (node (ref "J2") (pin "13") (pinfunction "13_13") (pintype "passive"))
      (node (ref "U1") (pin "33") (pinfunction "GPIO37/SPIDQS/FSPIQ/SUBSPIQ_33") (pintype "passive"))
    )
    (net (code "39") (name "/GPIO38") (class "Default")
      (node (ref "J2") (pin "12") (pinfunction "12_12") (pintype "passive"))
      (node (ref "U1") (pin "34") (pinfunction "GPIO38/FSPIWP/SUBSPIWP_34") (pintype "passive"))
    )
    (net (code "40") (name "/GPIO39") (class "Default")
      (node (ref "J2") (pin "11") (pinfunction "11_11") (pintype "passive"))
      (node (ref "U1") (pin "35") (pinfunction "MTCK/GPIO39/CLK_OUT3/SUBSPICS1_35") (pintype "passive"))
    )
    (net (code "41") (name "/GPIO40") (class "Default")
      (node (ref "J2") (pin "10") (pinfunction "10_10") (pintype "passive"))
      (node (ref "U1") (pin "36") (pinfunction "MTDO/GPIO40/CLK_OUT2_36") (pintype "passive"))
    )
    (net (code "42") (name "/GPIO41") (class "Default")
      (node (ref "J2") (pin "9") (pinfunction "9_9") (pintype "passive"))
      (node (ref "U1") (pin "37") (pinfunction "MTDI/GPIO41/CLK_OUT1_37") (pintype "passive"))
    )
    (net (code "43") (name "/GPIO42") (class "Default")
      (node (ref "J2") (pin "8") (pinfunction "8_8") (pintype "passive"))
      (node (ref "U1") (pin "38") (pinfunction "MTMS/GPIO42_38") (pintype "passive"))
    )
    (net (code "44") (name "/GPIO45") (class "Default")
      (node (ref "J2") (pin "5") (pinfunction "5_5") (pintype "passive"))
      (node (ref "U1") (pin "41") (pinfunction "GPIO45_41") (pintype "passive"))
    )
    (net (code "45") (name "/GPIO46") (class "Default")
      (node (ref "J2") (pin "4") (pinfunction "4_4") (pintype "passive"))
      (node (ref "U1") (pin "44") (pinfunction "GPIO46_44") (pintype "passive"))
    )
    (net (code "46") (name "/GPIO47") (class "Default")
      (node (ref "J2") (pin "24") (pinfunction "24_24") (pintype "passive"))
      (node (ref "U1") (pin "27") (pinfunction "GPIO47/SPICLK_P_DIFF/SUBSPICLK_P_DIFF_27") (pintype "passive"))
    )
    (net (code "47") (name "/GPIO48") (class "Default")
      (node (ref "J2") (pin "23") (pinfunction "23_23") (pintype "passive"))
      (node (ref "U1") (pin "30") (pinfunction "GPIO48/SPICLK_N_DIFF/SUBSPICLK_N_DIFF_30") (pintype "passive"))
    )
    (net (code "48") (name "/RTS_FTDI") (class "Default")
      (node (ref "Q1") (pin "2") (pinfunction "E_2") (pintype "passive"))
      (node (ref "R10") (pin "1") (pinfunction "1_1") (pintype "passive"))
      (node (ref "U2") (pin "19") (pinfunction "~{RTS}_19") (pintype "passive"))
    )
    (net (code "49") (name "/RXD_FTDI") (class "Default")
      (node (ref "R23") (pin "2") (pinfunction "2_2") (pintype "passive"))
      (node (ref "U2") (pin "1") (pinfunction "RXD_1") (pintype "passive"))
    )
    (net (code "50") (name "/TXD_FTDI") (class "Default")
      (node (ref "R22") (pin "2") (pinfunction "2_2") (pintype "passive"))
      (node (ref "U2") (pin "17") (pinfunction "TXD_17") (pintype "passive"))
    )
    (net (code "51") (name "/U0RXD") (class "Default")
      (node (ref "J2") (pin "6") (pinfunction "6_6") (pintype "passive"))
      (node (ref "R22") (pin "1") (pinfunction "1_1") (pintype "passive"))
      (node (ref "U1") (pin "40") (pinfunction "U0RXD/GPIO44/CLK_OUT2_40") (pintype "passive"))
    )
    (net (code "52") (name "/U0TXD") (class "Default")
      (node (ref "J2") (pin "7") (pinfunction "7_7") (pintype "passive"))
      (node (ref "R23") (pin "1") (pinfunction "1_1") (pintype "passive"))
      (node (ref "U1") (pin "39") (pinfunction "U0TXD/GPIO43/CLK_OUT1_39") (pintype "passive"))
    )
    (net (code "53") (name "/USBC1_N") (class "Default")
      (node (ref "D2") (pin "2") (pinfunction "2_2") (pintype "passive"))
      (node (ref "J3") (pin "A7") (pinfunction "DN1_A7") (pintype "passive"))
      (node (ref "J3") (pin "B7") (pinfunction "DN2_B7") (pintype "passive"))
      (node (ref "R15") (pin "1") (pinfunction "1_1") (pintype "passive"))
    )
    (net (code "54") (name "/USBC1_P") (class "Default")
      (node (ref "D3") (pin "2") (pinfunction "2_2") (pintype "passive"))
      (node (ref "J3") (pin "A6") (pinfunction "DP1_A6") (pintype "passive"))
      (node (ref "J3") (pin "B6") (pinfunction "DP2_B6") (pintype "passive"))
      (node (ref "R16") (pin "1") (pinfunction "1_1") (pintype "passive"))
    )
    (net (code "55") (name "/USBC2_N") (class "Default")
      (node (ref "D7") (pin "2") (pinfunction "2_2") (pintype "passive"))
      (node (ref "J4") (pin "A7") (pinfunction "DN1_A7") (pintype "passive"))
      (node (ref "J4") (pin "B7") (pinfunction "DN2_B7") (pintype "passive"))
      (node (ref "R25") (pin "1") (pinfunction "1_1") (pintype "passive"))
    )
    (net (code "56") (name "/USBC2_P") (class "Default")
      (node (ref "D8") (pin "2") (pinfunction "2_2") (pintype "passive"))
      (node (ref "J4") (pin "A6") (pinfunction "DP1_A6") (pintype "passive"))
      (node (ref "J4") (pin "B6") (pinfunction "DP2_B6") (pintype "passive"))
      (node (ref "R26") (pin "1") (pinfunction "1_1") (pintype "passive"))
    )
    (net (code "57") (name "/VBUS_SENSE") (class "Default")
      (node (ref "R19") (pin "1") (pinfunction "1_1") (pintype "passive"))
      (node (ref "R24") (pin "2") (pinfunction "2_2") (pintype "passive"))
      (node (ref "U2") (pin "16") (pinfunction "CBUS3_16") (pintype "passive"))
    )
    (net (code "58") (name "/VCC_FTDI") (class "Default")
      (node (ref "C14") (pin "2") (pinfunction "2_2") (pintype "passive"))
      (node (ref "C15") (pin "2") (pinfunction "2_2") (pintype "passive"))
      (node (ref "R12") (pin "2") (pinfunction "2_2") (pintype "passive"))
      (node (ref "R13") (pin "2") (pinfunction "2_2") (pintype "passive"))
      (node (ref "U2") (pin "12") (pinfunction "VCC_12") (pintype "passive"))
    )
    (net (code "59") (name "3V3") (class "Default")
      (node (ref "C12") (pin "1") (pinfunction "1_1") (pintype "passive"))
      (node (ref "C13") (pin "1") (pinfunction "1_1") (pintype "passive"))
      (node (ref "C7") (pin "2") (pinfunction "2_2") (pintype "passive"))
      (node (ref "C8") (pin "2") (pinfunction "2_2") (pintype "passive"))
      (node (ref "J1") (pin "2") (pinfunction "2_2") (pintype "passive"))
      (node (ref "J2") (pin "2") (pinfunction "2_2") (pintype "passive"))
      (node (ref "J5") (pin "1") (pinfunction "1_1") (pintype "passive"))
      (node (ref "R13") (pin "1") (pinfunction "1_1") (pintype "passive"))
      (node (ref "R14") (pin "1") (pinfunction "1_1") (pintype "passive"))
      (node (ref "R4") (pin "2") (pinfunction "2_2") (pintype "passive"))
      (node (ref "U1") (pin "3") (pinfunction "3V3_3") (pintype "passive"))
    )
    (net (code "60") (name "3V3_REG") (class "Default")
      (node (ref "C4") (pin "2") (pinfunction "2_2") (pintype "passive"))
      (node (ref "C5") (pin "2") (pinfunction "2_2") (pintype "passive"))
      (node (ref "J5") (pin "2") (pinfunction "2_2") (pintype "passive"))
      (node (ref "U3") (pin "3") (pinfunction "OUT_3") (pintype "power_in"))
    )
    (net (code "61") (name "5V") (class "Default")
      (node (ref "C10") (pin "2") (pinfunction "2_2") (pintype "passive"))
      (node (ref "C3") (pin "2") (pinfunction "2_2") (pintype "passive"))
      (node (ref "J1") (pin "22") (pinfunction "22_22") (pintype "passive"))
      (node (ref "J6") (pin "2") (pinfunction "2_2") (pintype "passive"))
      (node (ref "R1") (pin "2") (pinfunction "2_2") (pintype "passive"))
      (node (ref "R12") (pin "1") (pinfunction "1_1") (pintype "passive"))
      (node (ref "U3") (pin "1") (pinfunction "IN_1") (pintype "power_in"))
    )
    (net (code "62") (name "5V_VBUS1") (class "Default")
      (node (ref "C6") (pin "1") (pinfunction "1_1") (pintype "passive"))
      (node (ref "D1") (pin "2") (pinfunction "2_2") (pintype "passive"))
      (node (ref "J3") (pin "A4B9") (pinfunction "A4B9_VBUS_A4B9") (pintype "passive"))
      (node (ref "J3") (pin "B4A9") (pinfunction "B4A9_VBUS_B4A9") (pintype "passive"))
      (node (ref "J6") (pin "1") (pinfunction "1_1") (pintype "passive"))
      (node (ref "R19") (pin "2") (pinfunction "2_2") (pintype "passive"))
    )
    (net (code "63") (name "5V_VBUS2") (class "Default")
      (node (ref "C11") (pin "1") (pinfunction "1_1") (pintype "passive"))
      (node (ref "D4") (pin "2") (pinfunction "2_2") (pintype "passive"))
      (node (ref "J4") (pin "A4B9") (pinfunction "A4B9_VBUS_A4B9") (pintype "passive"))
      (node (ref "J4") (pin "B4A9") (pinfunction "B4A9_VBUS_B4A9") (pintype "passive"))
      (node (ref "J6") (pin "3") (pinfunction "3_3") (pintype "passive"))
    )
    (net (code "64") (name "GND") (class "Default")
      (node (ref "C10") (pin "1") (pinfunction "1_1") (pintype "passive"))
      (node (ref "C11") (pin "2") (pinfunction "2_2") (pintype "passive"))
      (node (ref "C12") (pin "2") (pinfunction "2_2") (pintype "passive"))
      (node (ref "C13") (pin "2") (pinfunction "2_2") (pintype "passive"))
      (node (ref "C14") (pin "1") (pinfunction "1_1") (pintype "passive"))
      (node (ref "C15") (pin "1") (pinfunction "1_1") (pintype "passive"))
      (node (ref "C16") (pin "2") (pinfunction "2_2") (pintype "passive"))
      (node (ref "C17") (pin "2") (pinfunction "2_2") (pintype "passive"))
      (node (ref "C18") (pin "2") (pinfunction "2_2") (pintype "passive"))
      (node (ref "C2") (pin "1") (pinfunction "1_1") (pintype "passive"))
      (node (ref "C3") (pin "1") (pinfunction "1_1") (pintype "passive"))
      (node (ref "C4") (pin "1") (pinfunction "1_1") (pintype "passive"))
      (node (ref "C5") (pin "1") (pinfunction "1_1") (pintype "passive"))
      (node (ref "C6") (pin "2") (pinfunction "2_2") (pintype "passive"))
      (node (ref "C7") (pin "1") (pinfunction "1_1") (pintype "passive"))
      (node (ref "C8") (pin "1") (pinfunction "1_1") (pintype "passive"))
      (node (ref "C9") (pin "1") (pinfunction "1_1") (pintype "passive"))
      (node (ref "D1") (pin "1") (pinfunction "1_1") (pintype "passive"))
      (node (ref "D2") (pin "1") (pinfunction "1_1") (pintype "passive"))
      (node (ref "D3") (pin "1") (pinfunction "1_1") (pintype "passive"))
      (node (ref "D4") (pin "1") (pinfunction "1_1") (pintype "passive"))
      (node (ref "D5") (pin "2") (pinfunction "2_2") (pintype "passive"))
      (node (ref "D6") (pin "2") (pinfunction "2_2") (pintype "passive"))
      (node (ref "D7") (pin "1") (pinfunction "1_1") (pintype "passive"))
      (node (ref "D8") (pin "1") (pinfunction "1_1") (pintype "passive"))
      (node (ref "J1") (pin "1") (pinfunction "1_1") (pintype "passive"))
      (node (ref "J1") (pin "23") (pinfunction "23_23") (pintype "passive"))
      (node (ref "J2") (pin "1") (pinfunction "1_1") (pintype "passive"))
      (node (ref "J2") (pin "22") (pinfunction "22_22") (pintype "passive"))
      (node (ref "J3") (pin "A1B12") (pinfunction "A1B12_GND_A1B12") (pintype "passive"))
      (node (ref "J3") (pin "B1A12") (pinfunction "B1A12_GND_B1A12") (pintype "passive"))
      (node (ref "J3") (pin "S1") (pinfunction "SHIELD_S1_S1") (pintype "passive"))
      (node (ref "J3") (pin "S2") (pinfunction "SHIELD_S2_S2") (pintype "passive"))
      (node (ref "J3") (pin "S3") (pinfunction "SHIELD_S3_S3") (pintype "passive"))
      (node (ref "J3") (pin "S4") (pinfunction "SHIELD_S4_S4") (pintype "passive"))
      (node (ref "J4") (pin "A1B12") (pinfunction "A1B12_GND_A1B12") (pintype "passive"))
      (node (ref "J4") (pin "B1A12") (pinfunction "B1A12_GND_B1A12") (pintype "passive"))
      (node (ref "J4") (pin "S1") (pinfunction "SHIELD_S1_S1") (pintype "passive"))
      (node (ref "J4") (pin "S2") (pinfunction "SHIELD_S2_S2") (pintype "passive"))
      (node (ref "J4") (pin "S3") (pinfunction "SHIELD_S3_S3") (pintype "passive"))
      (node (ref "J4") (pin "S4") (pinfunction "SHIELD_S4_S4") (pintype "passive"))
      (node (ref "R2") (pin "1") (pinfunction "1_1") (pintype "passive"))
      (node (ref "R21") (pin "2") (pinfunction "2_2") (pintype "passive"))
      (node (ref "R24") (pin "1") (pinfunction "1_1") (pintype "passive"))
      (node (ref "R3") (pin "1") (pinfunction "1_1") (pintype "passive"))
      (node (ref "R6") (pin "1") (pinfunction "1_1") (pintype "passive"))
      (node (ref "R7") (pin "1") (pinfunction "1_1") (pintype "passive"))
      (node (ref "SW1") (pin "1") (pinfunction "1_1") (pintype "passive"))
      (node (ref "SW1") (pin "2") (pinfunction "2_2") (pintype "passive"))
      (node (ref "SW2") (pin "1") (pinfunction "1_1") (pintype "passive"))
      (node (ref "SW2") (pin "2") (pinfunction "2_2") (pintype "passive"))
      (node (ref "U1") (pin "1") (pinfunction "GND_01_1") (pintype "passive"))
      (node (ref "U1") (pin "2") (pinfunction "GND_02_2") (pintype "passive"))
      (node (ref "U1") (pin "42") (pinfunction "GND_42") (pintype "passive"))
      (node (ref "U1") (pin "43") (pinfunction "GND_43") (pintype "passive"))
      (node (ref "U1") (pin "46") (pinfunction "GND_46_46") (pintype "passive"))
      (node (ref "U1") (pin "47") (pinfunction "GND_47_47") (pintype "passive"))
      (node (ref "U1") (pin "48") (pinfunction "GND_48_48") (pintype "passive"))
      (node (ref "U1") (pin "49") (pinfunction "GND_49_49") (pintype "passive"))
      (node (ref "U1") (pin "50") (pinfunction "GND_50_50") (pintype "passive"))
      (node (ref "U1") (pin "51") (pinfunction "GND_51_51") (pintype "passive"))
      (node (ref "U1") (pin "52") (pinfunction "GND_52_52") (pintype "passive"))
      (node (ref "U1") (pin "53") (pinfunction "GND_53_53") (pintype "passive"))
      (node (ref "U1") (pin "54") (pinfunction "GND_54_54") (pintype "passive"))
      (node (ref "U1") (pin "55") (pinfunction "GND_55_55") (pintype "passive"))
      (node (ref "U1") (pin "56") (pinfunction "GND_56_56") (pintype "passive"))
      (node (ref "U1") (pin "57") (pinfunction "GND_57_57") (pintype "passive"))
      (node (ref "U1") (pin "58") (pinfunction "GND_58_58") (pintype "passive"))
      (node (ref "U1") (pin "59") (pinfunction "GND_59_59") (pintype "passive"))
      (node (ref "U1") (pin "60") (pinfunction "GND_60_60") (pintype "passive"))
      (node (ref "U1") (pin "61") (pinfunction "GND_61_61") (pintype "passive"))
      (node (ref "U1") (pin "62") (pinfunction "GND_62_62") (pintype "passive"))
      (node (ref "U1") (pin "63") (pinfunction "GND_63_63") (pintype "passive"))
      (node (ref "U1") (pin "64") (pinfunction "GND_64_64") (pintype "passive"))
      (node (ref "U1") (pin "65") (pinfunction "GND_65_65") (pintype "passive"))
      (node (ref "U1") (pin "66") (pinfunction "GND_66_66") (pintype "passive"))
      (node (ref "U1") (pin "67") (pinfunction "GND_67_67") (pintype "passive"))
      (node (ref "U1") (pin "68") (pinfunction "GND_68_68") (pintype "passive"))
      (node (ref "U1") (pin "69") (pinfunction "GND_69_69") (pintype "passive"))
      (node (ref "U1") (pin "70") (pinfunction "GND_70_70") (pintype "passive"))
      (node (ref "U1") (pin "71") (pinfunction "GND_71_71") (pintype "passive"))
      (node (ref "U1") (pin "72") (pinfunction "GND_72_72") (pintype "passive"))
      (node (ref "U1") (pin "73") (pinfunction "GND_73_73") (pintype "passive"))
      (node (ref "U2") (pin "13") (pinfunction "GND_13") (pintype "passive"))
      (node (ref "U2") (pin "21") (pinfunction "GND_21") (pintype "passive"))
      (node (ref "U2") (pin "3") (pinfunction "GND_3") (pintype "passive"))
      (node (ref "U3") (pin "2") (pinfunction "GND_2") (pintype "power_in"))
      (node (ref "U3") (pin "4") (pinfunction "GND_4") (pintype "power_in"))
    )
    (net (code "65") (name "Net-(D5-Pad1)") (class "Default")
      (node (ref "D5") (pin "1") (pinfunction "1_1") (pintype "passive"))
      (node (ref "R4") (pin "1") (pinfunction "1_1") (pintype "passive"))
    )
    (net (code "66") (name "Net-(D6-Pad1)") (class "Default")
      (node (ref "D6") (pin "1") (pinfunction "1_1") (pintype "passive"))
      (node (ref "R5") (pin "1") (pinfunction "1_1") (pintype "passive"))
    )
    (net (code "67") (name "Net-(J3-CC1)") (class "Default")
      (node (ref "J3") (pin "A5") (pinfunction "CC1_A5") (pintype "passive"))
      (node (ref "R3") (pin "2") (pinfunction "2_2") (pintype "passive"))
    )
    (net (code "68") (name "Net-(J3-CC2)") (class "Default")
      (node (ref "J3") (pin "B5") (pinfunction "CC2_B5") (pintype "passive"))
      (node (ref "R2") (pin "2") (pinfunction "2_2") (pintype "passive"))
    )
    (net (code "69") (name "Net-(J4-CC1)") (class "Default")
      (node (ref "J4") (pin "A5") (pinfunction "CC1_A5") (pintype "passive"))
      (node (ref "R7") (pin "2") (pinfunction "2_2") (pintype "passive"))
    )
    (net (code "70") (name "Net-(J4-CC2)") (class "Default")
      (node (ref "J4") (pin "B5") (pinfunction "CC2_B5") (pintype "passive"))
      (node (ref "R6") (pin "2") (pinfunction "2_2") (pintype "passive"))
    )
    (net (code "71") (name "Net-(Q1-B)") (class "Default")
      (node (ref "Q1") (pin "1") (pinfunction "B_1") (pintype "passive"))
      (node (ref "R9") (pin "2") (pinfunction "2_2") (pintype "passive"))
    )
    (net (code "72") (name "Net-(Q1-C)") (class "Default")
      (node (ref "Q1") (pin "3") (pinfunction "C_3") (pintype "passive"))
      (node (ref "R8") (pin "1") (pinfunction "1_1") (pintype "passive"))
    )
    (net (code "73") (name "Net-(Q2-B)") (class "Default")
      (node (ref "Q2") (pin "1") (pinfunction "B_1") (pintype "passive"))
      (node (ref "R10") (pin "2") (pinfunction "2_2") (pintype "passive"))
    )
    (net (code "74") (name "Net-(Q2-C)") (class "Default")
      (node (ref "Q2") (pin "3") (pinfunction "C_3") (pintype "passive"))
      (node (ref "R11") (pin "1") (pinfunction "1_1") (pintype "passive"))
    )
    (net (code "75") (name "Net-(U2-CBUS0)") (class "Default")
      (node (ref "R21") (pin "1") (pinfunction "1_1") (pintype "passive"))
      (node (ref "U2") (pin "15") (pinfunction "CBUS0_15") (pintype "passive"))
    )
    (net (code "76") (name "unconnected-(C1-Pad1)") (class "Default")
      (node (ref "C1") (pin "1") (pinfunction "1_1") (pintype "passive"))
    )
    (net (code "77") (name "unconnected-(C1-Pad2)") (class "Default")
      (node (ref "C1") (pin "2") (pinfunction "2_2") (pintype "passive"))
    )
    (net (code "78") (name "unconnected-(J1-Pad24)") (class "Default")
      (node (ref "J1") (pin "24") (pinfunction "24_24") (pintype "passive+no_connect"))
    )
    (net (code "79") (name "unconnected-(J3-SBU1-PadA8)") (class "Default")
      (node (ref "J3") (pin "A8") (pinfunction "SBU1_A8") (pintype "passive+no_connect"))
    )
    (net (code "80") (name "unconnected-(J3-SBU2-PadB8)") (class "Default")
      (node (ref "J3") (pin "B8") (pinfunction "SBU2_B8") (pintype "passive+no_connect"))
    )
    (net (code "81") (name "unconnected-(J4-SBU1-PadA8)") (class "Default")
      (node (ref "J4") (pin "A8") (pinfunction "SBU1_A8") (pintype "passive+no_connect"))
    )
    (net (code "82") (name "unconnected-(J4-SBU2-PadB8)") (class "Default")
      (node (ref "J4") (pin "B8") (pinfunction "SBU2_B8") (pintype "passive+no_connect"))
    )
    (net (code "83") (name "unconnected-(U2-CBUS1-Pad14)") (class "Default")
      (node (ref "U2") (pin "14") (pinfunction "CBUS1_14") (pintype "passive+no_connect"))
    )
    (net (code "84") (name "unconnected-(U2-CBUS2-Pad7)") (class "Default")
      (node (ref "U2") (pin "7") (pinfunction "CBUS2_7") (pintype "passive+no_connect"))
    )
    (net (code "85") (name "unconnected-(U2-~{CTS}-Pad6)") (class "Default")
      (node (ref "U2") (pin "6") (pinfunction "~{CTS}_6") (pintype "passive+no_connect"))
    )
    (net (code "86") (name "unconnected-(U2-~{DCD}-Pad5)") (class "Default")
      (node (ref "U2") (pin "5") (pinfunction "~{DCD}_5") (pintype "passive+no_connect"))
    )
    (net (code "87") (name "unconnected-(U2-~{DSR}-Pad4)") (class "Default")
      (node (ref "U2") (pin "4") (pinfunction "~{DSR}_4") (pintype "passive+no_connect"))
    )
    (net (code "88") (name "unconnected-(U2-~{RI}-Pad2)") (class "Default")
      (node (ref "U2") (pin "2") (pinfunction "~{RI}_2") (pintype "passive+no_connect"))
    )
  )
)
